# Final_PCB_2.net
KiCad netlist of a schematic drawn in EAGLE
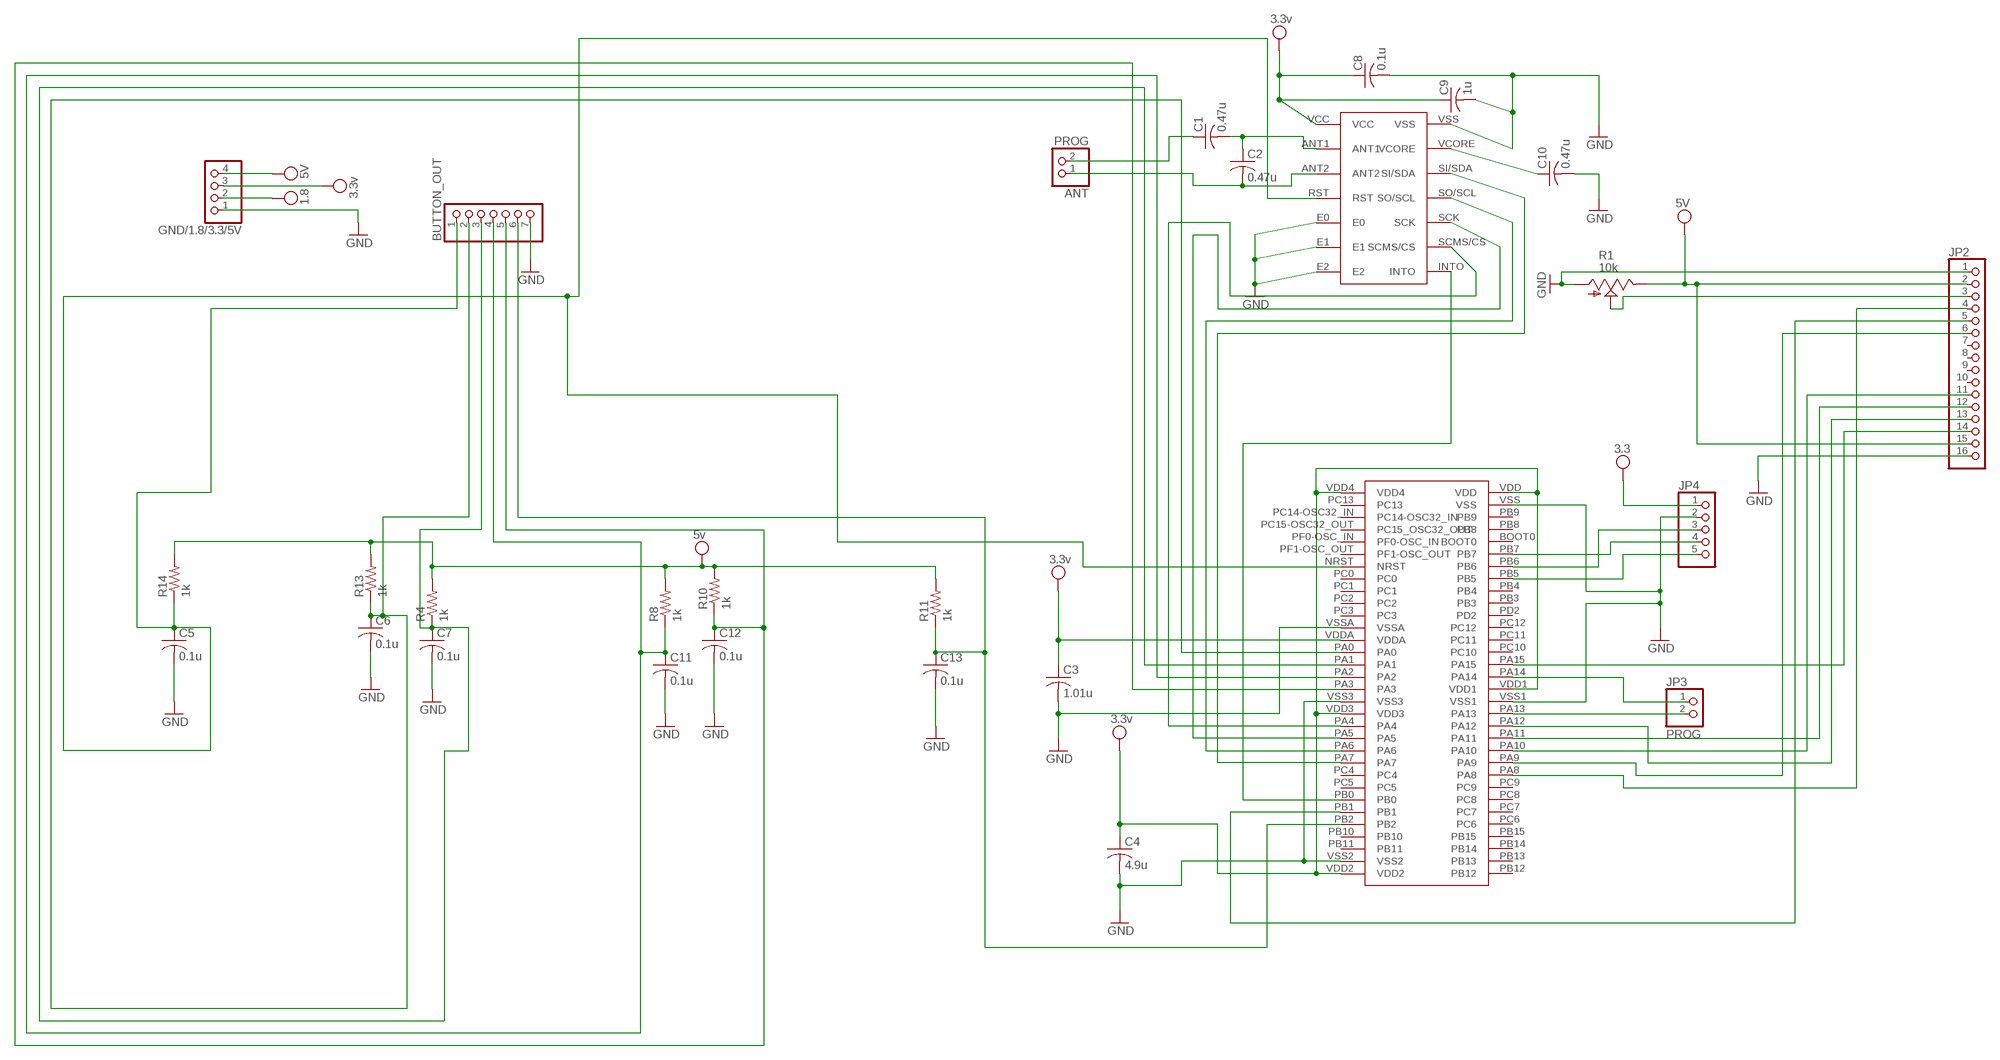
[diagram p0: schematic, sheet 1]

(export (version "E")
  (design (tool "Eeschema 10.0.6"))
  (components
    (comp (ref "ANT")
      (value "PROG")
      (footprint "eagle-import:1X02")
      (libsource (lib "eagle-import") (part "PINHD-1X2"))
    )
    (comp (ref "BUTTON_OUT")
      (value "PINHD-1X7")
      (footprint "eagle-import:1X07")
      (libsource (lib "eagle-import") (part "PINHD-1X7"))
    )
    (comp (ref "C1")
      (value "0.47u")
      (footprint "eagle-import:C0805")
      (libsource (lib "eagle-import") (part "C-USC0805"))
    )
    (comp (ref "C2")
      (value "0.47u")
      (footprint "eagle-import:C0805")
      (libsource (lib "eagle-import") (part "C-USC0805"))
    )
    (comp (ref "C3")
      (value "1.01u")
      (footprint "eagle-import:C0805")
      (libsource (lib "eagle-import") (part "C-USC0805"))
    )
    (comp (ref "C4")
      (value "4.9u")
      (footprint "eagle-import:C0805")
      (libsource (lib "eagle-import") (part "C-USC0805"))
    )
    (comp (ref "C5")
      (value "0.1u")
      (footprint "eagle-import:C0805")
      (libsource (lib "eagle-import") (part "C-USC0805"))
    )
    (comp (ref "C6")
      (value "0.1u")
      (footprint "eagle-import:C0805")
      (libsource (lib "eagle-import") (part "C-USC0805"))
    )
    (comp (ref "C7")
      (value "0.1u")
      (footprint "eagle-import:C0805")
      (libsource (lib "eagle-import") (part "C-USC0805"))
    )
    (comp (ref "C8")
      (value "0.1u")
      (footprint "eagle-import:C0805")
      (libsource (lib "eagle-import") (part "C-USC0805"))
    )
    (comp (ref "C9")
      (value "1u")
      (footprint "eagle-import:C0805")
      (libsource (lib "eagle-import") (part "C-USC0805"))
    )
    (comp (ref "C10")
      (value "0.47u")
      (footprint "eagle-import:C0805")
      (libsource (lib "eagle-import") (part "C-USC0805"))
    )
    (comp (ref "C11")
      (value "0.1u")
      (footprint "eagle-import:C0805")
      (libsource (lib "eagle-import") (part "C-USC0805"))
    )
    (comp (ref "C12")
      (value "0.1u")
      (footprint "eagle-import:C0805")
      (libsource (lib "eagle-import") (part "C-USC0805"))
    )
    (comp (ref "C13")
      (value "0.1u")
      (footprint "eagle-import:C0805")
      (libsource (lib "eagle-import") (part "C-USC0805"))
    )
    (comp (ref "GND/1.8/3.3/5V")
      (value "PINHD-1X4/90")
      (footprint "eagle-import:1X04_90")
      (libsource (lib "eagle-import") (part "PINHD-1X4/90"))
    )
    (comp (ref "JP2")
      (value "PINHD-1X16")
      (footprint "eagle-import:1X16")
      (libsource (lib "eagle-import") (part "PINHD-1X16"))
    )
    (comp (ref "JP3")
      (value "PROG")
      (footprint "eagle-import:1X02")
      (libsource (lib "eagle-import") (part "PINHD-1X2"))
    )
    (comp (ref "JP4")
      (value "PINHD-1X5")
      (footprint "eagle-import:1X05")
      (libsource (lib "eagle-import") (part "PINHD-1X5"))
    )
    (comp (ref "R1")
      (value "10k")
      (footprint "eagle-import:B64Y")
      (libsource (lib "eagle-import") (part "TRIM_US-B64Y"))
    )
    (comp (ref "R4")
      (value "1k")
      (footprint "eagle-import:R0805")
      (libsource (lib "eagle-import") (part "R-US_R0805"))
    )
    (comp (ref "R8")
      (value "1k")
      (footprint "eagle-import:R0805")
      (libsource (lib "eagle-import") (part "R-US_R0805"))
    )
    (comp (ref "R10")
      (value "1k")
      (footprint "eagle-import:R0805")
      (libsource (lib "eagle-import") (part "R-US_R0805"))
    )
    (comp (ref "R11")
      (value "1k")
      (footprint "eagle-import:R0805")
      (libsource (lib "eagle-import") (part "R-US_R0805"))
    )
    (comp (ref "R13")
      (value "1k")
      (footprint "eagle-import:R0805")
      (libsource (lib "eagle-import") (part "R-US_R0805"))
    )
    (comp (ref "R14")
      (value "1k")
      (footprint "eagle-import:R0805")
      (libsource (lib "eagle-import") (part "R-US_R0805"))
    )
    (comp (ref "U$2")
      (value "LQFP64")
      (footprint "eagle-import:LQFP64")
      (libsource (lib "eagle-import") (part "LQFP64"))
    )
    (comp (ref "U$7")
      (value "RF430CL330H")
      (footprint "eagle-import:RF430CL330H")
      (libsource (lib "eagle-import") (part "RF430CL330H"))
    )
  )
  (nets
    (net (code "1") (name "1.8") (class "Default")
      (node (ref "GND/1.8/3.3/5V") (pin "2") (pinfunction "2_2") (pintype "passive"))
    )
    (net (code "2") (name "3.3") (class "Default")
      (node (ref "C3") (pin "1") (pinfunction "1_1") (pintype "passive"))
      (node (ref "C4") (pin "1") (pinfunction "1_1") (pintype "passive"))
      (node (ref "C8") (pin "1") (pinfunction "1_1") (pintype "passive"))
      (node (ref "C9") (pin "1") (pinfunction "1_1") (pintype "passive"))
      (node (ref "GND/1.8/3.3/5V") (pin "3") (pinfunction "3_3") (pintype "passive"))
      (node (ref "JP4") (pin "1") (pinfunction "1_1") (pintype "passive"))
      (node (ref "U$2") (pin "VDD") (pinfunction "VDD_VDD") (pintype "bidirectional"))
      (node (ref "U$2") (pin "VDD1") (pinfunction "VDD1_VDD1") (pintype "bidirectional"))
      (node (ref "U$2") (pin "VDD2") (pinfunction "VDD2_VDD2") (pintype "bidirectional"))
      (node (ref "U$2") (pin "VDD3") (pinfunction "VDD3_VDD3") (pintype "bidirectional"))
      (node (ref "U$2") (pin "VDD4") (pinfunction "VDD4_VDD4") (pintype "bidirectional"))
      (node (ref "U$2") (pin "VDDA") (pinfunction "VDDA_VDDA") (pintype "bidirectional"))
      (node (ref "U$7") (pin "VCC") (pinfunction "VCC_VCC") (pintype "bidirectional"))
    )
    (net (code "3") (name "5V") (class "Default")
      (node (ref "GND/1.8/3.3/5V") (pin "4") (pinfunction "4_4") (pintype "passive"))
      (node (ref "JP2") (pin "15") (pinfunction "15_15") (pintype "passive"))
      (node (ref "JP2") (pin "2") (pinfunction "2_2") (pintype "passive"))
      (node (ref "R1") (pin "E") (pinfunction "E_E") (pintype "passive"))
      (node (ref "R10") (pin "2") (pinfunction "2_2") (pintype "passive"))
      (node (ref "R11") (pin "2") (pinfunction "2_2") (pintype "passive"))
      (node (ref "R13") (pin "2") (pinfunction "2_2") (pintype "passive"))
      (node (ref "R14") (pin "2") (pinfunction "2_2") (pintype "passive"))
      (node (ref "R4") (pin "2") (pinfunction "2_2") (pintype "passive"))
      (node (ref "R8") (pin "2") (pinfunction "2_2") (pintype "passive"))
    )
    (net (code "4") (name "GND") (class "Default")
      (node (ref "BUTTON_OUT") (pin "7") (pinfunction "7_7") (pintype "passive"))
      (node (ref "C10") (pin "2") (pinfunction "2_2") (pintype "passive"))
      (node (ref "C11") (pin "2") (pinfunction "2_2") (pintype "passive"))
      (node (ref "C12") (pin "2") (pinfunction "2_2") (pintype "passive"))
      (node (ref "C13") (pin "2") (pinfunction "2_2") (pintype "passive"))
      (node (ref "C3") (pin "2") (pinfunction "2_2") (pintype "passive"))
      (node (ref "C4") (pin "2") (pinfunction "2_2") (pintype "passive"))
      (node (ref "C5") (pin "2") (pinfunction "2_2") (pintype "passive"))
      (node (ref "C6") (pin "2") (pinfunction "2_2") (pintype "passive"))
      (node (ref "C7") (pin "2") (pinfunction "2_2") (pintype "passive"))
      (node (ref "C8") (pin "2") (pinfunction "2_2") (pintype "passive"))
      (node (ref "C9") (pin "2") (pinfunction "2_2") (pintype "passive"))
      (node (ref "GND/1.8/3.3/5V") (pin "1") (pinfunction "1_1") (pintype "passive"))
      (node (ref "JP2") (pin "1") (pinfunction "1_1") (pintype "passive"))
      (node (ref "JP2") (pin "16") (pinfunction "16_16") (pintype "passive"))
      (node (ref "JP4") (pin "2") (pinfunction "2_2") (pintype "passive"))
      (node (ref "R1") (pin "A") (pinfunction "A_A") (pintype "passive"))
      (node (ref "U$2") (pin "VSS") (pinfunction "VSS_VSS") (pintype "bidirectional"))
      (node (ref "U$2") (pin "VSS1") (pinfunction "VSS1_VSS1") (pintype "bidirectional"))
      (node (ref "U$2") (pin "VSS2") (pinfunction "VSS2_VSS2") (pintype "bidirectional"))
      (node (ref "U$2") (pin "VSS3") (pinfunction "VSS3_VSS3") (pintype "bidirectional"))
      (node (ref "U$2") (pin "VSSA") (pinfunction "VSSA_VSSA") (pintype "bidirectional"))
      (node (ref "U$7") (pin "E0") (pinfunction "E0_E0") (pintype "bidirectional"))
      (node (ref "U$7") (pin "E1") (pinfunction "E1_E1") (pintype "bidirectional"))
      (node (ref "U$7") (pin "E2") (pinfunction "E2_E2") (pintype "bidirectional"))
      (node (ref "U$7") (pin "VSS") (pinfunction "VSS_VSS") (pintype "bidirectional"))
    )
    (net (code "5") (name "Net-(ANT-Pad1)") (class "Default")
      (node (ref "ANT") (pin "1") (pinfunction "1_1") (pintype "passive"))
      (node (ref "C2") (pin "2") (pinfunction "2_2") (pintype "passive"))
      (node (ref "U$7") (pin "ANT2") (pinfunction "ANT2_ANT2") (pintype "bidirectional"))
    )
    (net (code "6") (name "Net-(ANT-Pad2)") (class "Default")
      (node (ref "ANT") (pin "2") (pinfunction "2_2") (pintype "passive"))
      (node (ref "C1") (pin "1") (pinfunction "1_1") (pintype "passive"))
    )
    (net (code "7") (name "Net-(BUTTON_OUT-Pad1)") (class "Default")
      (node (ref "BUTTON_OUT") (pin "1") (pinfunction "1_1") (pintype "passive"))
      (node (ref "C5") (pin "1") (pinfunction "1_1") (pintype "passive"))
      (node (ref "R14") (pin "1") (pinfunction "1_1") (pintype "passive"))
      (node (ref "U$2") (pin "NRST") (pinfunction "NRST_NRST") (pintype "bidirectional"))
      (node (ref "U$7") (pin "RST") (pinfunction "RST_RST") (pintype "bidirectional"))
    )
    (net (code "8") (name "Net-(BUTTON_OUT-Pad2)") (class "Default")
      (node (ref "BUTTON_OUT") (pin "2") (pinfunction "2_2") (pintype "passive"))
      (node (ref "C6") (pin "1") (pinfunction "1_1") (pintype "passive"))
      (node (ref "R13") (pin "1") (pinfunction "1_1") (pintype "passive"))
      (node (ref "U$2") (pin "PA0") (pinfunction "PA0_PA0") (pintype "bidirectional"))
    )
    (net (code "9") (name "Net-(BUTTON_OUT-Pad3)") (class "Default")
      (node (ref "BUTTON_OUT") (pin "3") (pinfunction "3_3") (pintype "passive"))
      (node (ref "C7") (pin "1") (pinfunction "1_1") (pintype "passive"))
      (node (ref "R4") (pin "1") (pinfunction "1_1") (pintype "passive"))
      (node (ref "U$2") (pin "PA1") (pinfunction "PA1_PA1") (pintype "bidirectional"))
    )
    (net (code "10") (name "Net-(BUTTON_OUT-Pad4)") (class "Default")
      (node (ref "BUTTON_OUT") (pin "4") (pinfunction "4_4") (pintype "passive"))
      (node (ref "C11") (pin "1") (pinfunction "1_1") (pintype "passive"))
      (node (ref "R8") (pin "1") (pinfunction "1_1") (pintype "passive"))
      (node (ref "U$2") (pin "PA2") (pinfunction "PA2_PA2") (pintype "bidirectional"))
    )
    (net (code "11") (name "Net-(BUTTON_OUT-Pad5)") (class "Default")
      (node (ref "BUTTON_OUT") (pin "5") (pinfunction "5_5") (pintype "passive"))
      (node (ref "C12") (pin "1") (pinfunction "1_1") (pintype "passive"))
      (node (ref "R10") (pin "1") (pinfunction "1_1") (pintype "passive"))
      (node (ref "U$2") (pin "PA3") (pinfunction "PA3_PA3") (pintype "bidirectional"))
    )
    (net (code "12") (name "Net-(BUTTON_OUT-Pad6)") (class "Default")
      (node (ref "BUTTON_OUT") (pin "6") (pinfunction "6_6") (pintype "passive"))
      (node (ref "C13") (pin "1") (pinfunction "1_1") (pintype "passive"))
      (node (ref "R11") (pin "1") (pinfunction "1_1") (pintype "passive"))
      (node (ref "U$2") (pin "PB2") (pinfunction "PB2_PB2") (pintype "bidirectional"))
    )
    (net (code "13") (name "Net-(C1-Pad2)") (class "Default")
      (node (ref "C1") (pin "2") (pinfunction "2_2") (pintype "passive"))
      (node (ref "C2") (pin "1") (pinfunction "1_1") (pintype "passive"))
      (node (ref "U$7") (pin "ANT1") (pinfunction "ANT1_ANT1") (pintype "bidirectional"))
    )
    (net (code "14") (name "Net-(C10-Pad1)") (class "Default")
      (node (ref "C10") (pin "1") (pinfunction "1_1") (pintype "passive"))
      (node (ref "U$7") (pin "VCORE") (pinfunction "VCORE_VCORE") (pintype "bidirectional"))
    )
    (net (code "15") (name "Net-(JP2-Pad3)") (class "Default")
      (node (ref "JP2") (pin "3") (pinfunction "3_3") (pintype "passive"))
      (node (ref "R1") (pin "S") (pinfunction "S_S") (pintype "passive"))
    )
    (net (code "16") (name "Net-(JP2-Pad4)") (class "Default")
      (node (ref "JP2") (pin "4") (pinfunction "4_4") (pintype "passive"))
      (node (ref "U$2") (pin "PA8") (pinfunction "PA8_PA8") (pintype "bidirectional"))
    )
    (net (code "17") (name "Net-(JP2-Pad5)") (class "Default")
      (node (ref "JP2") (pin "5") (pinfunction "5_5") (pintype "passive"))
      (node (ref "U$2") (pin "PB1") (pinfunction "PB1_PB1") (pintype "bidirectional"))
    )
    (net (code "18") (name "Net-(JP2-Pad6)") (class "Default")
      (node (ref "JP2") (pin "6") (pinfunction "6_6") (pintype "passive"))
      (node (ref "U$2") (pin "PA9") (pinfunction "PA9_PA9") (pintype "bidirectional"))
    )
    (net (code "19") (name "Net-(JP2-Pad11)") (class "Default")
      (node (ref "JP2") (pin "11") (pinfunction "11_11") (pintype "passive"))
      (node (ref "U$2") (pin "PA10") (pinfunction "PA10_PA10") (pintype "bidirectional"))
    )
    (net (code "20") (name "Net-(JP2-Pad12)") (class "Default")
      (node (ref "JP2") (pin "12") (pinfunction "12_12") (pintype "passive"))
      (node (ref "U$2") (pin "PA11") (pinfunction "PA11_PA11") (pintype "bidirectional"))
    )
    (net (code "21") (name "Net-(JP2-Pad13)") (class "Default")
      (node (ref "JP2") (pin "13") (pinfunction "13_13") (pintype "passive"))
      (node (ref "U$2") (pin "PA12") (pinfunction "PA12_PA12") (pintype "bidirectional"))
    )
    (net (code "22") (name "Net-(JP2-Pad14)") (class "Default")
      (node (ref "JP2") (pin "14") (pinfunction "14_14") (pintype "passive"))
      (node (ref "U$2") (pin "PA15") (pinfunction "PA15_PA15") (pintype "bidirectional"))
    )
    (net (code "23") (name "Net-(JP3-Pad1)") (class "Default")
      (node (ref "JP3") (pin "1") (pinfunction "1_1") (pintype "passive"))
      (node (ref "U$2") (pin "PA14") (pinfunction "PA14_PA14") (pintype "bidirectional"))
    )
    (net (code "24") (name "Net-(JP3-Pad2)") (class "Default")
      (node (ref "JP3") (pin "2") (pinfunction "2_2") (pintype "passive"))
      (node (ref "U$2") (pin "PA13") (pinfunction "PA13_PA13") (pintype "bidirectional"))
    )
    (net (code "25") (name "Net-(JP4-Pad3)") (class "Default")
      (node (ref "JP4") (pin "3") (pinfunction "3_3") (pintype "passive"))
      (node (ref "U$2") (pin "PB6") (pinfunction "PB6_PB6") (pintype "bidirectional"))
    )
    (net (code "26") (name "Net-(JP4-Pad4)") (class "Default")
      (node (ref "JP4") (pin "4") (pinfunction "4_4") (pintype "passive"))
      (node (ref "U$2") (pin "PB7") (pinfunction "PB7_PB7") (pintype "bidirectional"))
    )
    (net (code "27") (name "Net-(JP4-Pad5)") (class "Default")
      (node (ref "JP4") (pin "5") (pinfunction "5_5") (pintype "passive"))
      (node (ref "U$2") (pin "PB5") (pinfunction "PB5_PB5") (pintype "bidirectional"))
    )
    (net (code "28") (name "Net-(U$2-PadPA4)") (class "Default")
      (node (ref "U$2") (pin "PA4") (pinfunction "PA4_PA4") (pintype "bidirectional"))
      (node (ref "U$7") (pin "SCMS/CS") (pinfunction "SCMS/CS_SCMS/CS") (pintype "bidirectional"))
    )
    (net (code "29") (name "Net-(U$2-PadPA5)") (class "Default")
      (node (ref "U$2") (pin "PA5") (pinfunction "PA5_PA5") (pintype "bidirectional"))
      (node (ref "U$7") (pin "SCK") (pinfunction "SCK_SCK") (pintype "bidirectional"))
    )
    (net (code "30") (name "Net-(U$2-PadPA6)") (class "Default")
      (node (ref "U$2") (pin "PA6") (pinfunction "PA6_PA6") (pintype "bidirectional"))
      (node (ref "U$7") (pin "SO/SCL") (pinfunction "SO/SCL_SO/SCL") (pintype "bidirectional"))
    )
    (net (code "31") (name "Net-(U$2-PadPA7)") (class "Default")
      (node (ref "U$2") (pin "PA7") (pinfunction "PA7_PA7") (pintype "bidirectional"))
      (node (ref "U$7") (pin "SI/SDA") (pinfunction "SI/SDA_SI/SDA") (pintype "bidirectional"))
    )
    (net (code "32") (name "Net-(U$2-PadPB0)") (class "Default")
      (node (ref "U$2") (pin "PB0") (pinfunction "PB0_PB0") (pintype "bidirectional"))
      (node (ref "U$7") (pin "INTO") (pinfunction "INTO_INTO") (pintype "bidirectional"))
    )
    (net (code "33") (name "unconnected-(JP2-Pad7)") (class "Default")
      (node (ref "JP2") (pin "7") (pinfunction "7_7") (pintype "passive"))
    )
    (net (code "34") (name "unconnected-(JP2-Pad8)") (class "Default")
      (node (ref "JP2") (pin "8") (pinfunction "8_8") (pintype "passive"))
    )
    (net (code "35") (name "unconnected-(JP2-Pad9)") (class "Default")
      (node (ref "JP2") (pin "9") (pinfunction "9_9") (pintype "passive"))
    )
    (net (code "36") (name "unconnected-(JP2-Pad10)") (class "Default")
      (node (ref "JP2") (pin "10") (pinfunction "10_10") (pintype "passive"))
    )
    (net (code "37") (name "unconnected-(U$2-PC15_OSC32_OUT-PadPC15-OSC32_OUT)") (class "Default")
      (node (ref "U$2") (pin "PC15-OSC32_OUT") (pinfunction "PC15_OSC32_OUT_PC15-OSC32_OUT") (pintype "bidirectional"))
    )
    (net (code "38") (name "unconnected-(U$2-PadBOOT0)") (class "Default")
      (node (ref "U$2") (pin "BOOT0") (pinfunction "BOOT0_BOOT0") (pintype "bidirectional"))
    )
    (net (code "39") (name "unconnected-(U$2-PadPB3)") (class "Default")
      (node (ref "U$2") (pin "PB3") (pinfunction "PB3_PB3") (pintype "bidirectional"))
    )
    (net (code "40") (name "unconnected-(U$2-PadPB4)") (class "Default")
      (node (ref "U$2") (pin "PB4") (pinfunction "PB4_PB4") (pintype "bidirectional"))
    )
    (net (code "41") (name "unconnected-(U$2-PadPB8)") (class "Default")
      (node (ref "U$2") (pin "PB8") (pinfunction "PB8_PB8") (pintype "bidirectional"))
    )
    (net (code "42") (name "unconnected-(U$2-PadPB9)") (class "Default")
      (node (ref "U$2") (pin "PB9") (pinfunction "PB9_PB9") (pintype "bidirectional"))
    )
    (net (code "43") (name "unconnected-(U$2-PadPB10)") (class "Default")
      (node (ref "U$2") (pin "PB10") (pinfunction "PB10_PB10") (pintype "bidirectional"))
    )
    (net (code "44") (name "unconnected-(U$2-PadPB11)") (class "Default")
      (node (ref "U$2") (pin "PB11") (pinfunction "PB11_PB11") (pintype "bidirectional"))
    )
    (net (code "45") (name "unconnected-(U$2-PadPB12)") (class "Default")
      (node (ref "U$2") (pin "PB12") (pinfunction "PB12_PB12") (pintype "bidirectional"))
    )
    (net (code "46") (name "unconnected-(U$2-PadPB13)") (class "Default")
      (node (ref "U$2") (pin "PB13") (pinfunction "PB13_PB13") (pintype "bidirectional"))
    )
    (net (code "47") (name "unconnected-(U$2-PadPB14)") (class "Default")
      (node (ref "U$2") (pin "PB14") (pinfunction "PB14_PB14") (pintype "bidirectional"))
    )
    (net (code "48") (name "unconnected-(U$2-PadPB15)") (class "Default")
      (node (ref "U$2") (pin "PB15") (pinfunction "PB15_PB15") (pintype "bidirectional"))
    )
    (net (code "49") (name "unconnected-(U$2-PadPC0)") (class "Default")
      (node (ref "U$2") (pin "PC0") (pinfunction "PC0_PC0") (pintype "bidirectional"))
    )
    (net (code "50") (name "unconnected-(U$2-PadPC1)") (class "Default")
      (node (ref "U$2") (pin "PC1") (pinfunction "PC1_PC1") (pintype "bidirectional"))
    )
    (net (code "51") (name "unconnected-(U$2-PadPC2)") (class "Default")
      (node (ref "U$2") (pin "PC2") (pinfunction "PC2_PC2") (pintype "bidirectional"))
    )
    (net (code "52") (name "unconnected-(U$2-PadPC3)") (class "Default")
      (node (ref "U$2") (pin "PC3") (pinfunction "PC3_PC3") (pintype "bidirectional"))
    )
    (net (code "53") (name "unconnected-(U$2-PadPC4)") (class "Default")
      (node (ref "U$2") (pin "PC4") (pinfunction "PC4_PC4") (pintype "bidirectional"))
    )
    (net (code "54") (name "unconnected-(U$2-PadPC5)") (class "Default")
      (node (ref "U$2") (pin "PC5") (pinfunction "PC5_PC5") (pintype "bidirectional"))
    )
    (net (code "55") (name "unconnected-(U$2-PadPC6)") (class "Default")
      (node (ref "U$2") (pin "PC6") (pinfunction "PC6_PC6") (pintype "bidirectional"))
    )
    (net (code "56") (name "unconnected-(U$2-PadPC7)") (class "Default")
      (node (ref "U$2") (pin "PC7") (pinfunction "PC7_PC7") (pintype "bidirectional"))
    )
    (net (code "57") (name "unconnected-(U$2-PadPC8)") (class "Default")
      (node (ref "U$2") (pin "PC8") (pinfunction "PC8_PC8") (pintype "bidirectional"))
    )
    (net (code "58") (name "unconnected-(U$2-PadPC9)") (class "Default")
      (node (ref "U$2") (pin "PC9") (pinfunction "PC9_PC9") (pintype "bidirectional"))
    )
    (net (code "59") (name "unconnected-(U$2-PadPC10)") (class "Default")
      (node (ref "U$2") (pin "PC10") (pinfunction "PC10_PC10") (pintype "bidirectional"))
    )
    (net (code "60") (name "unconnected-(U$2-PadPC11)") (class "Default")
      (node (ref "U$2") (pin "PC11") (pinfunction "PC11_PC11") (pintype "bidirectional"))
    )
    (net (code "61") (name "unconnected-(U$2-PadPC12)") (class "Default")
      (node (ref "U$2") (pin "PC12") (pinfunction "PC12_PC12") (pintype "bidirectional"))
    )
    (net (code "62") (name "unconnected-(U$2-PadPC13)") (class "Default")
      (node (ref "U$2") (pin "PC13") (pinfunction "PC13_PC13") (pintype "bidirectional"))
    )
    (net (code "63") (name "unconnected-(U$2-PadPC14-OSC32_IN)") (class "Default")
      (node (ref "U$2") (pin "PC14-OSC32_IN") (pinfunction "PC14-OSC32_IN_PC14-OSC32_IN") (pintype "bidirectional"))
    )
    (net (code "64") (name "unconnected-(U$2-PadPD2)") (class "Default")
      (node (ref "U$2") (pin "PD2") (pinfunction "PD2_PD2") (pintype "bidirectional"))
    )
    (net (code "65") (name "unconnected-(U$2-PadPF0-OSC_IN)") (class "Default")
      (node (ref "U$2") (pin "PF0-OSC_IN") (pinfunction "PF0-OSC_IN_PF0-OSC_IN") (pintype "bidirectional"))
    )
    (net (code "66") (name "unconnected-(U$2-PadPF1-OSC_OUT)") (class "Default")
      (node (ref "U$2") (pin "PF1-OSC_OUT") (pinfunction "PF1-OSC_OUT_PF1-OSC_OUT") (pintype "bidirectional"))
    )
  )
)
